# schematic_eda.net
KiCad netlist of a schematic drawn in EasyEDA
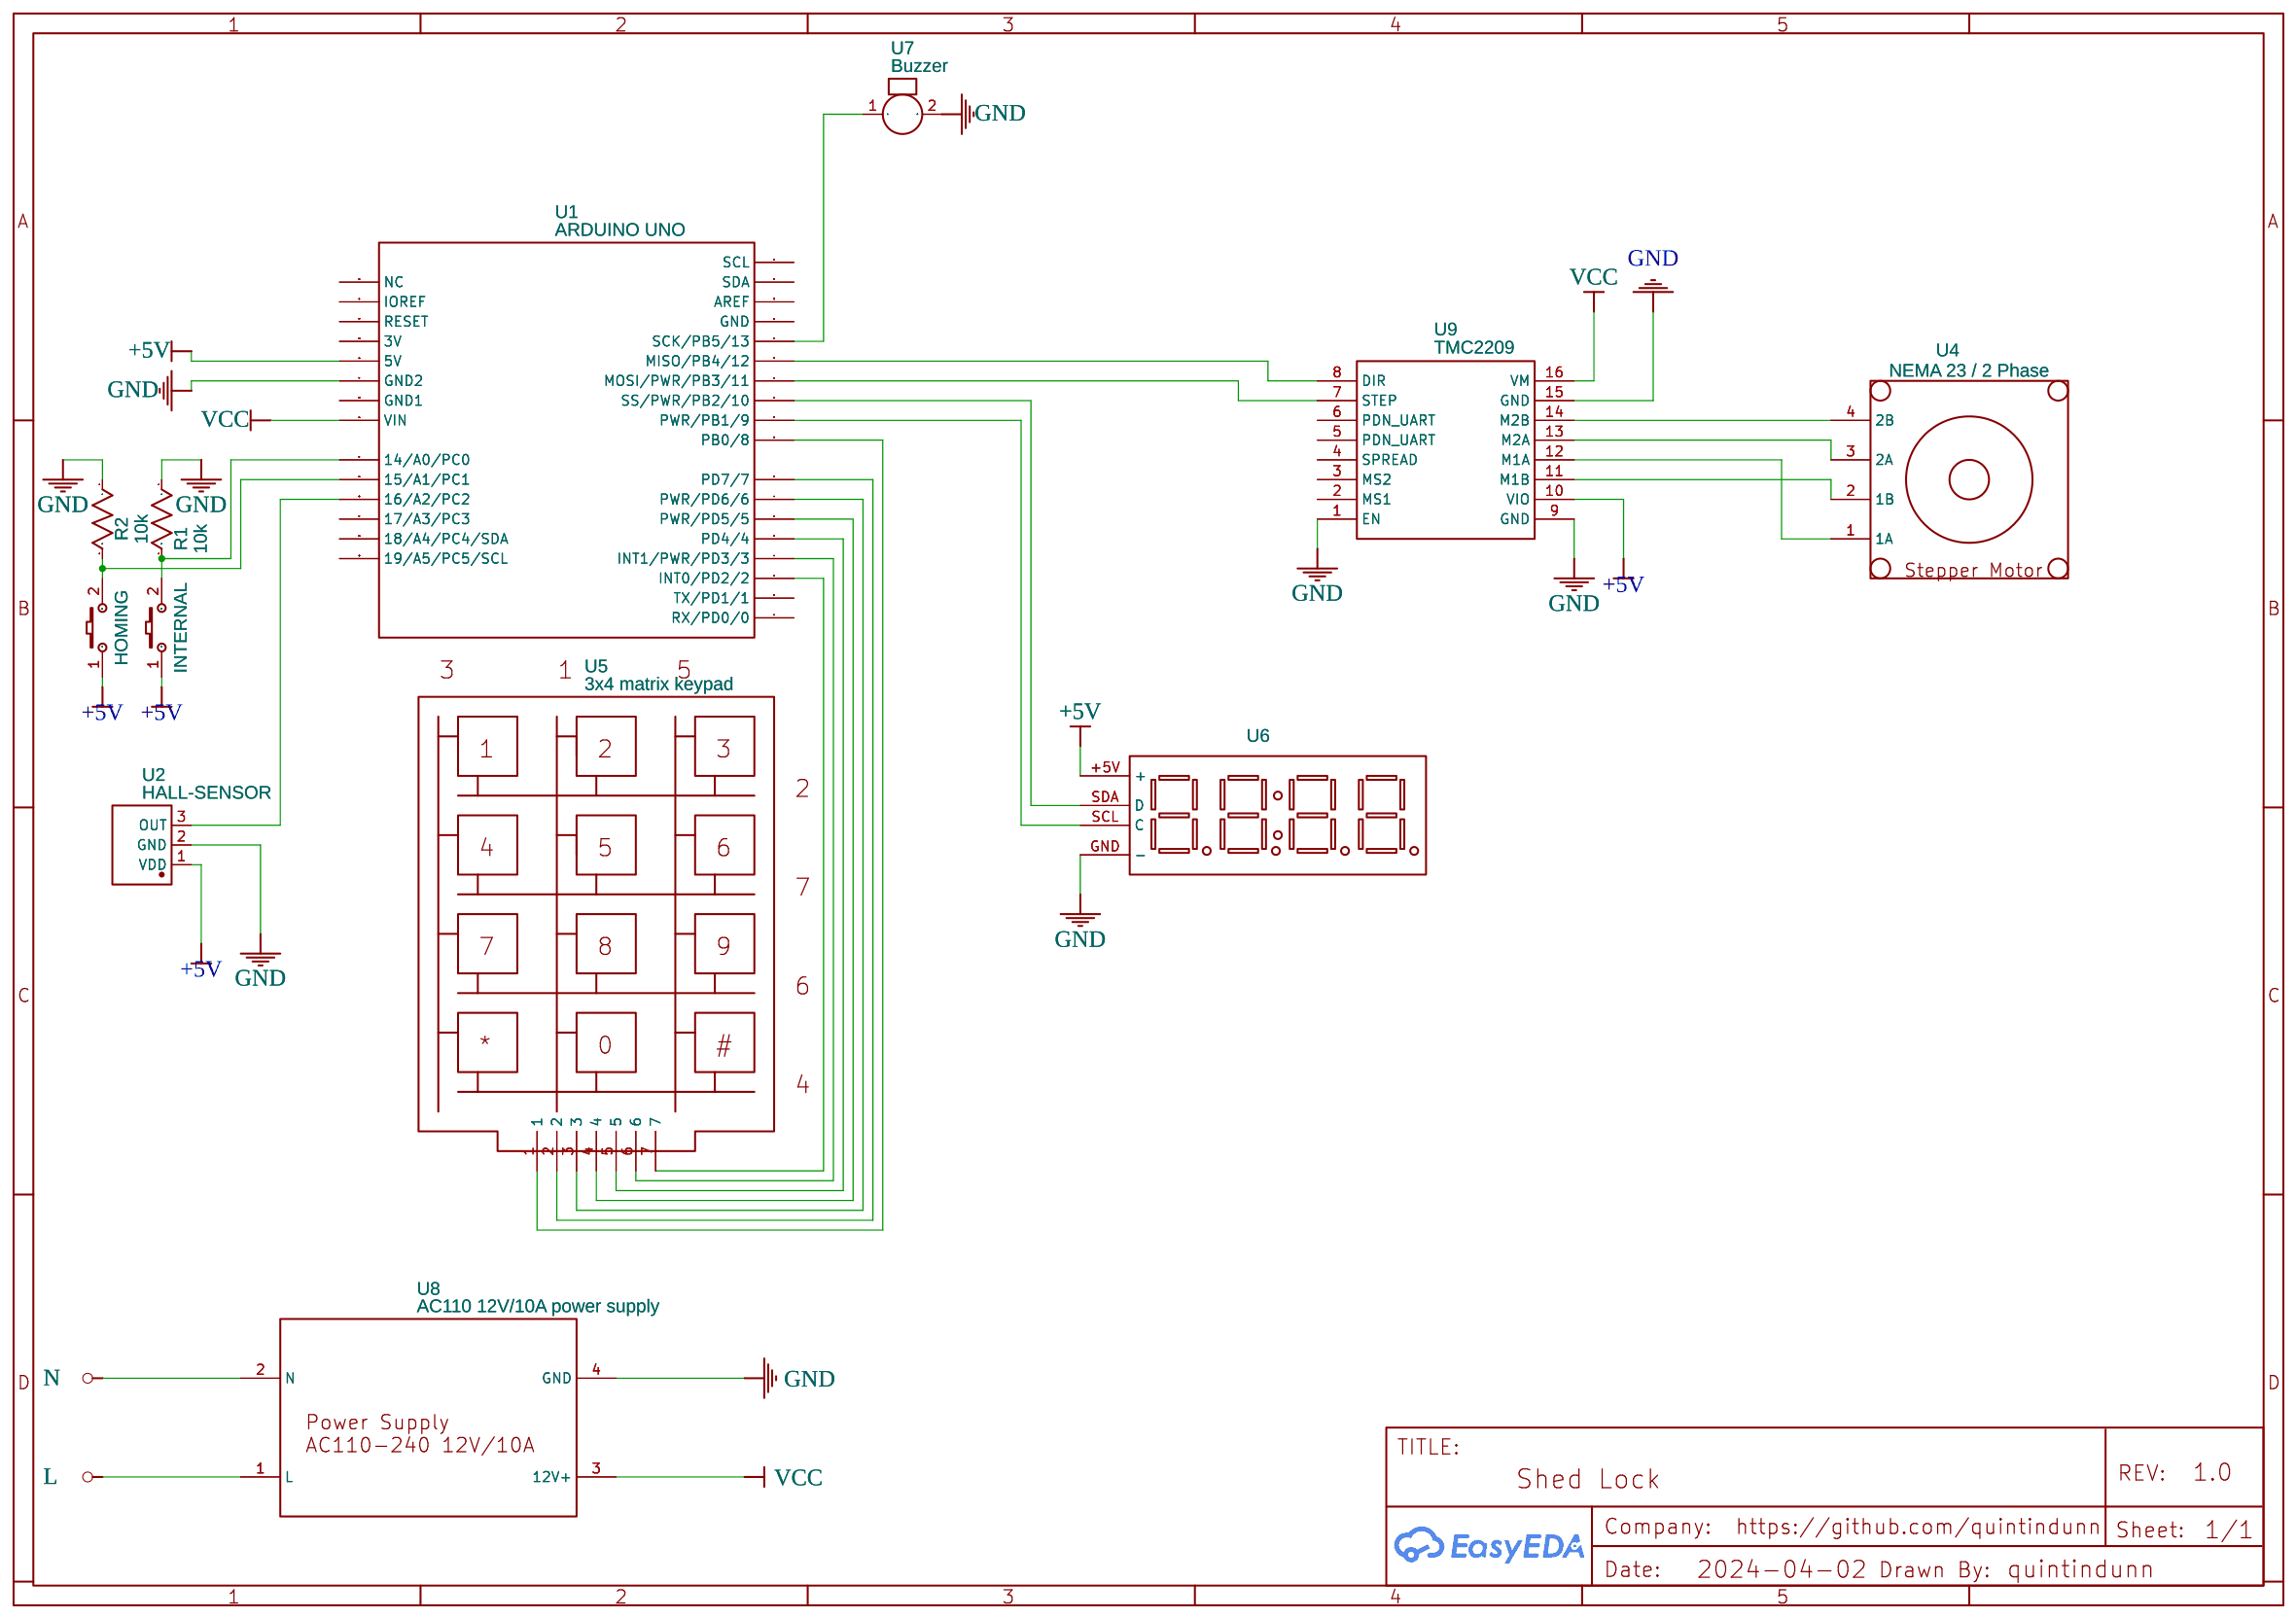
[diagram p0: schematic sheet]

(export (version "E")
  (design (tool "Eeschema 10.0.6"))
  (components
    (comp (ref "HOMING")
      (value "K2-3.6×6.1_SMD")
      (fields (field (name "Manufacturer Part") "K2-1107ST-A4SW-06"))
      (libsource (lib "") (part "K2-3.6×6.1_SMD_1"))
    )
    (comp (ref "INTERNAL")
      (value "K2-3.6×6.1_SMD")
      (fields (field (name "Manufacturer Part") "K2-1107ST-A4SW-06"))
      (libsource (lib "") (part "K2-3.6×6.1_SMD"))
    )
    (comp (ref "R1") (value "10k") (libsource (lib "") (part "R_0603_US")))
    (comp (ref "R2") (value "10k") (libsource (lib "") (part "R_0603_US")))
    (comp (ref "U1") (value "ARDUINO UNO") (libsource (lib "") (part "ARDUINO UNO")))
    (comp (ref "U2")
      (value "HALL-SENSOR")
      (fields
        (field (name "Manufacturer Part") "US5881EUA-AAA-000-BU")
        (field (name "Manufacturer") "Melexis(比利时迈来芯)")
      )
      (libsource (lib "") (part "HALL-SENSOR-US5881-ZA"))
    )
    (comp (ref "U4")
      (value "NEMA 23 / 2 Phase")
      (libsource (lib "") (part "Stepper Motor{colon} Bipolar, 200 Steps/Rev, 3.2V, 2.8 A/Phase"))
    )
    (comp (ref "U5") (value "3x4 matrix keypad") (libsource (lib "") (part "3x4 matrix keypad")))
    (comp (ref "U6")
      (value "ADAFRUIT 4-DIGIT 7-SEGMENT DISPLAY WITH I2C BACKPACK")
      (libsource (lib "") (part "ADAFRUIT 4-DIGIT 7-SEGMENT DISPLAY WITH I2C BACKPACK"))
    )
    (comp (ref "U7") (value "Buzzer") (libsource (lib "") (part "Buzzer")))
    (comp (ref "U8")
      (value "AC110 12V/10A power supply")
      (libsource (lib "") (part "AC110 12V/2A power supply"))
    )
    (comp (ref "U9") (value "TMC2209") (libsource (lib "") (part "TMC2209")))
  )
  (nets
    (net (code "1") (name "+5V") (class "Default")
      (node (ref "HOMING") (pin "1") (pinfunction "1_1") (pintype "unspecified"))
      (node (ref "INTERNAL") (pin "1") (pinfunction "1_1") (pintype "unspecified"))
      (node (ref "U1") (pin "28") (pinfunction "5V_28") (pintype "passive"))
      (node (ref "U2") (pin "1") (pinfunction "VDD_1") (pintype "unspecified"))
      (node (ref "U6") (pin "+5V") (pinfunction "+_+5V") (pintype "unspecified"))
      (node (ref "U9") (pin "10") (pinfunction "VIO_10") (pintype "unspecified"))
    )
    (net (code "2") (name "GND") (class "Default")
      (node (ref "R1") (pin "1") (pinfunction "1_1") (pintype "unspecified"))
      (node (ref "R2") (pin "1") (pinfunction "1_1") (pintype "unspecified"))
      (node (ref "U1") (pin "27") (pinfunction "GND2_27") (pintype "passive"))
      (node (ref "U2") (pin "2") (pinfunction "GND_2") (pintype "unspecified"))
      (node (ref "U6") (pin "GND") (pinfunction "-_GND") (pintype "unspecified"))
      (node (ref "U7") (pin "2") (pinfunction "2_2") (pintype "unspecified"))
      (node (ref "U8") (pin "4") (pinfunction "GND_4") (pintype "unspecified"))
      (node (ref "U9") (pin "1") (pinfunction "EN_1") (pintype "unspecified"))
      (node (ref "U9") (pin "15") (pinfunction "GND_15") (pintype "unspecified"))
      (node (ref "U9") (pin "9") (pinfunction "GND_9") (pintype "unspecified"))
    )
    (net (code "3") (name "L") (class "Default")
      (node (ref "U8") (pin "1") (pinfunction "L_1") (pintype "unspecified"))
    )
    (net (code "4") (name "N") (class "Default")
      (node (ref "U8") (pin "2") (pinfunction "N_2") (pintype "unspecified"))
    )
    (net (code "5") (name "Net-(U1-14{slash}A0{slash}PC0)") (class "Default")
      (node (ref "INTERNAL") (pin "2") (pinfunction "2_2") (pintype "unspecified"))
      (node (ref "R1") (pin "2") (pinfunction "2_2") (pintype "unspecified"))
      (node (ref "U1") (pin "24") (pinfunction "14/A0/PC0_24") (pintype "unspecified"))
    )
    (net (code "6") (name "Net-(U1-15{slash}A1{slash}PC1)") (class "Default")
      (node (ref "HOMING") (pin "2") (pinfunction "2_2") (pintype "unspecified"))
      (node (ref "R2") (pin "2") (pinfunction "2_2") (pintype "unspecified"))
      (node (ref "U1") (pin "23") (pinfunction "15/A1/PC1_23") (pintype "unspecified"))
    )
    (net (code "7") (name "Net-(U1-16{slash}A2{slash}PC2)") (class "Default")
      (node (ref "U1") (pin "22") (pinfunction "16/A2/PC2_22") (pintype "unspecified"))
      (node (ref "U2") (pin "3") (pinfunction "OUT_3") (pintype "unspecified"))
    )
    (net (code "8") (name "Net-(U1-INT0{slash}PD2{slash}2)") (class "Default")
      (node (ref "U1") (pin "3") (pinfunction "INT0/PD2/2_3") (pintype "unspecified"))
      (node (ref "U5") (pin "7") (pinfunction "7_7") (pintype "unspecified"))
    )
    (net (code "9") (name "Net-(U1-INT1{slash}PWR{slash}PD3{slash}3)") (class "Default")
      (node (ref "U1") (pin "4") (pinfunction "INT1/PWR/PD3/3_4") (pintype "unspecified"))
      (node (ref "U5") (pin "6") (pinfunction "6_6") (pintype "unspecified"))
    )
    (net (code "10") (name "Net-(U1-MISO{slash}PB4{slash}12)") (class "Default")
      (node (ref "U1") (pin "13") (pinfunction "MISO/PB4/12_13") (pintype "unspecified"))
      (node (ref "U9") (pin "8") (pinfunction "DIR_8") (pintype "unspecified"))
    )
    (net (code "11") (name "Net-(U1-MOSI{slash}PWR{slash}PB3{slash}11)") (class "Default")
      (node (ref "U1") (pin "12") (pinfunction "MOSI/PWR/PB3/11_12") (pintype "unspecified"))
      (node (ref "U9") (pin "7") (pinfunction "STEP_7") (pintype "unspecified"))
    )
    (net (code "12") (name "Net-(U1-PB0{slash}8)") (class "Default")
      (node (ref "U1") (pin "9") (pinfunction "PB0/8_9") (pintype "unspecified"))
      (node (ref "U5") (pin "1") (pinfunction "1_1") (pintype "unspecified"))
    )
    (net (code "13") (name "Net-(U1-PD4{slash}4)") (class "Default")
      (node (ref "U1") (pin "5") (pinfunction "PD4/4_5") (pintype "unspecified"))
      (node (ref "U5") (pin "5") (pinfunction "5_5") (pintype "unspecified"))
    )
    (net (code "14") (name "Net-(U1-PD7{slash}7)") (class "Default")
      (node (ref "U1") (pin "8") (pinfunction "PD7/7_8") (pintype "unspecified"))
      (node (ref "U5") (pin "2") (pinfunction "2_2") (pintype "unspecified"))
    )
    (net (code "15") (name "Net-(U1-PWR{slash}PB1{slash}9)") (class "Default")
      (node (ref "U1") (pin "10") (pinfunction "PWR/PB1/9_10") (pintype "unspecified"))
      (node (ref "U6") (pin "SCL") (pinfunction "C_SCL") (pintype "unspecified"))
    )
    (net (code "16") (name "Net-(U1-PWR{slash}PD5{slash}5)") (class "Default")
      (node (ref "U1") (pin "6") (pinfunction "PWR/PD5/5_6") (pintype "unspecified"))
      (node (ref "U5") (pin "4") (pinfunction "4_4") (pintype "unspecified"))
    )
    (net (code "17") (name "Net-(U1-PWR{slash}PD6{slash}6)") (class "Default")
      (node (ref "U1") (pin "7") (pinfunction "PWR/PD6/6_7") (pintype "unspecified"))
      (node (ref "U5") (pin "3") (pinfunction "3_3") (pintype "unspecified"))
    )
    (net (code "18") (name "Net-(U1-SCK{slash}PB5{slash}13)") (class "Default")
      (node (ref "U1") (pin "14") (pinfunction "SCK/PB5/13_14") (pintype "unspecified"))
      (node (ref "U7") (pin "1") (pinfunction "1_1") (pintype "unspecified"))
    )
    (net (code "19") (name "Net-(U1-SS{slash}PWR{slash}PB2{slash}10)") (class "Default")
      (node (ref "U1") (pin "11") (pinfunction "SS/PWR/PB2/10_11") (pintype "unspecified"))
      (node (ref "U6") (pin "SDA") (pinfunction "D_SDA") (pintype "unspecified"))
    )
    (net (code "20") (name "Net-(U4-1A)") (class "Default")
      (node (ref "U4") (pin "1") (pinfunction "1A_1") (pintype "unspecified"))
      (node (ref "U9") (pin "12") (pinfunction "M1A_12") (pintype "unspecified"))
    )
    (net (code "21") (name "Net-(U4-1B)") (class "Default")
      (node (ref "U4") (pin "2") (pinfunction "1B_2") (pintype "unspecified"))
      (node (ref "U9") (pin "11") (pinfunction "M1B_11") (pintype "unspecified"))
    )
    (net (code "22") (name "Net-(U4-2A)") (class "Default")
      (node (ref "U4") (pin "3") (pinfunction "2A_3") (pintype "unspecified"))
      (node (ref "U9") (pin "13") (pinfunction "M2A_13") (pintype "unspecified"))
    )
    (net (code "23") (name "Net-(U4-2B)") (class "Default")
      (node (ref "U4") (pin "4") (pinfunction "2B_4") (pintype "unspecified"))
      (node (ref "U9") (pin "14") (pinfunction "M2B_14") (pintype "unspecified"))
    )
    (net (code "24") (name "VCC") (class "Default")
      (node (ref "U1") (pin "25") (pinfunction "VIN_25") (pintype "passive"))
      (node (ref "U8") (pin "3") (pinfunction "12V+_3") (pintype "unspecified"))
      (node (ref "U9") (pin "16") (pinfunction "VM_16") (pintype "unspecified"))
    )
    (net (code "25") (name "unconnected-(U1-3V-Pad29)") (class "Default")
      (node (ref "U1") (pin "29") (pinfunction "3V_29") (pintype "passive"))
    )
    (net (code "26") (name "unconnected-(U1-17{slash}A3{slash}PC3-Pad21)") (class "Default")
      (node (ref "U1") (pin "21") (pinfunction "17/A3/PC3_21") (pintype "unspecified"))
    )
    (net (code "27") (name "unconnected-(U1-18{slash}A4{slash}PC4{slash}SDA-Pad20)") (class "Default")
      (node (ref "U1") (pin "20") (pinfunction "18/A4/PC4/SDA_20") (pintype "unspecified"))
    )
    (net (code "28") (name "unconnected-(U1-19{slash}A5{slash}PC5{slash}SCL-Pad19)") (class "Default")
      (node (ref "U1") (pin "19") (pinfunction "19/A5/PC5/SCL_19") (pintype "unspecified"))
    )
    (net (code "29") (name "unconnected-(U1-AREF-Pad16)") (class "Default")
      (node (ref "U1") (pin "16") (pinfunction "AREF_16") (pintype "unspecified"))
    )
    (net (code "30") (name "unconnected-(U1-GND-Pad15)") (class "Default")
      (node (ref "U1") (pin "15") (pinfunction "GND_15") (pintype "passive"))
    )
    (net (code "31") (name "unconnected-(U1-GND1-Pad26)") (class "Default")
      (node (ref "U1") (pin "26") (pinfunction "GND1_26") (pintype "passive"))
    )
    (net (code "32") (name "unconnected-(U1-IOREF-Pad31)") (class "Default")
      (node (ref "U1") (pin "31") (pinfunction "IOREF_31") (pintype "unspecified"))
    )
    (net (code "33") (name "unconnected-(U1-NC-Pad32)") (class "Default")
      (node (ref "U1") (pin "32") (pinfunction "NC_32") (pintype "unspecified"))
    )
    (net (code "34") (name "unconnected-(U1-RESET-Pad30)") (class "Default")
      (node (ref "U1") (pin "30") (pinfunction "RESET_30") (pintype "unspecified"))
    )
    (net (code "35") (name "unconnected-(U1-RX{slash}PD0{slash}0-Pad1)") (class "Default")
      (node (ref "U1") (pin "1") (pinfunction "RX/PD0/0_1") (pintype "unspecified"))
    )
    (net (code "36") (name "unconnected-(U1-SCL-Pad18)") (class "Default")
      (node (ref "U1") (pin "18") (pinfunction "SCL_18") (pintype "unspecified"))
    )
    (net (code "37") (name "unconnected-(U1-SDA-Pad17)") (class "Default")
      (node (ref "U1") (pin "17") (pinfunction "SDA_17") (pintype "unspecified"))
    )
    (net (code "38") (name "unconnected-(U1-TX{slash}PD1{slash}1-Pad2)") (class "Default")
      (node (ref "U1") (pin "2") (pinfunction "TX/PD1/1_2") (pintype "unspecified"))
    )
    (net (code "39") (name "unconnected-(U9-MS1-Pad2)") (class "Default")
      (node (ref "U9") (pin "2") (pinfunction "MS1_2") (pintype "unspecified"))
    )
    (net (code "40") (name "unconnected-(U9-MS2-Pad3)") (class "Default")
      (node (ref "U9") (pin "3") (pinfunction "MS2_3") (pintype "unspecified"))
    )
    (net (code "41") (name "unconnected-(U9-PDN_UART-Pad5)") (class "Default")
      (node (ref "U9") (pin "5") (pinfunction "PDN_UART_5") (pintype "unspecified"))
    )
    (net (code "42") (name "unconnected-(U9-PDN_UART-Pad6)") (class "Default")
      (node (ref "U9") (pin "6") (pinfunction "PDN_UART_6") (pintype "unspecified"))
    )
    (net (code "43") (name "unconnected-(U9-SPREAD-Pad4)") (class "Default")
      (node (ref "U9") (pin "4") (pinfunction "SPREAD_4") (pintype "unspecified"))
    )
  )
)
